# P1AM-ISOLATED-2X2-GPIO.net
KiCad netlist of a schematic drawn in EAGLE
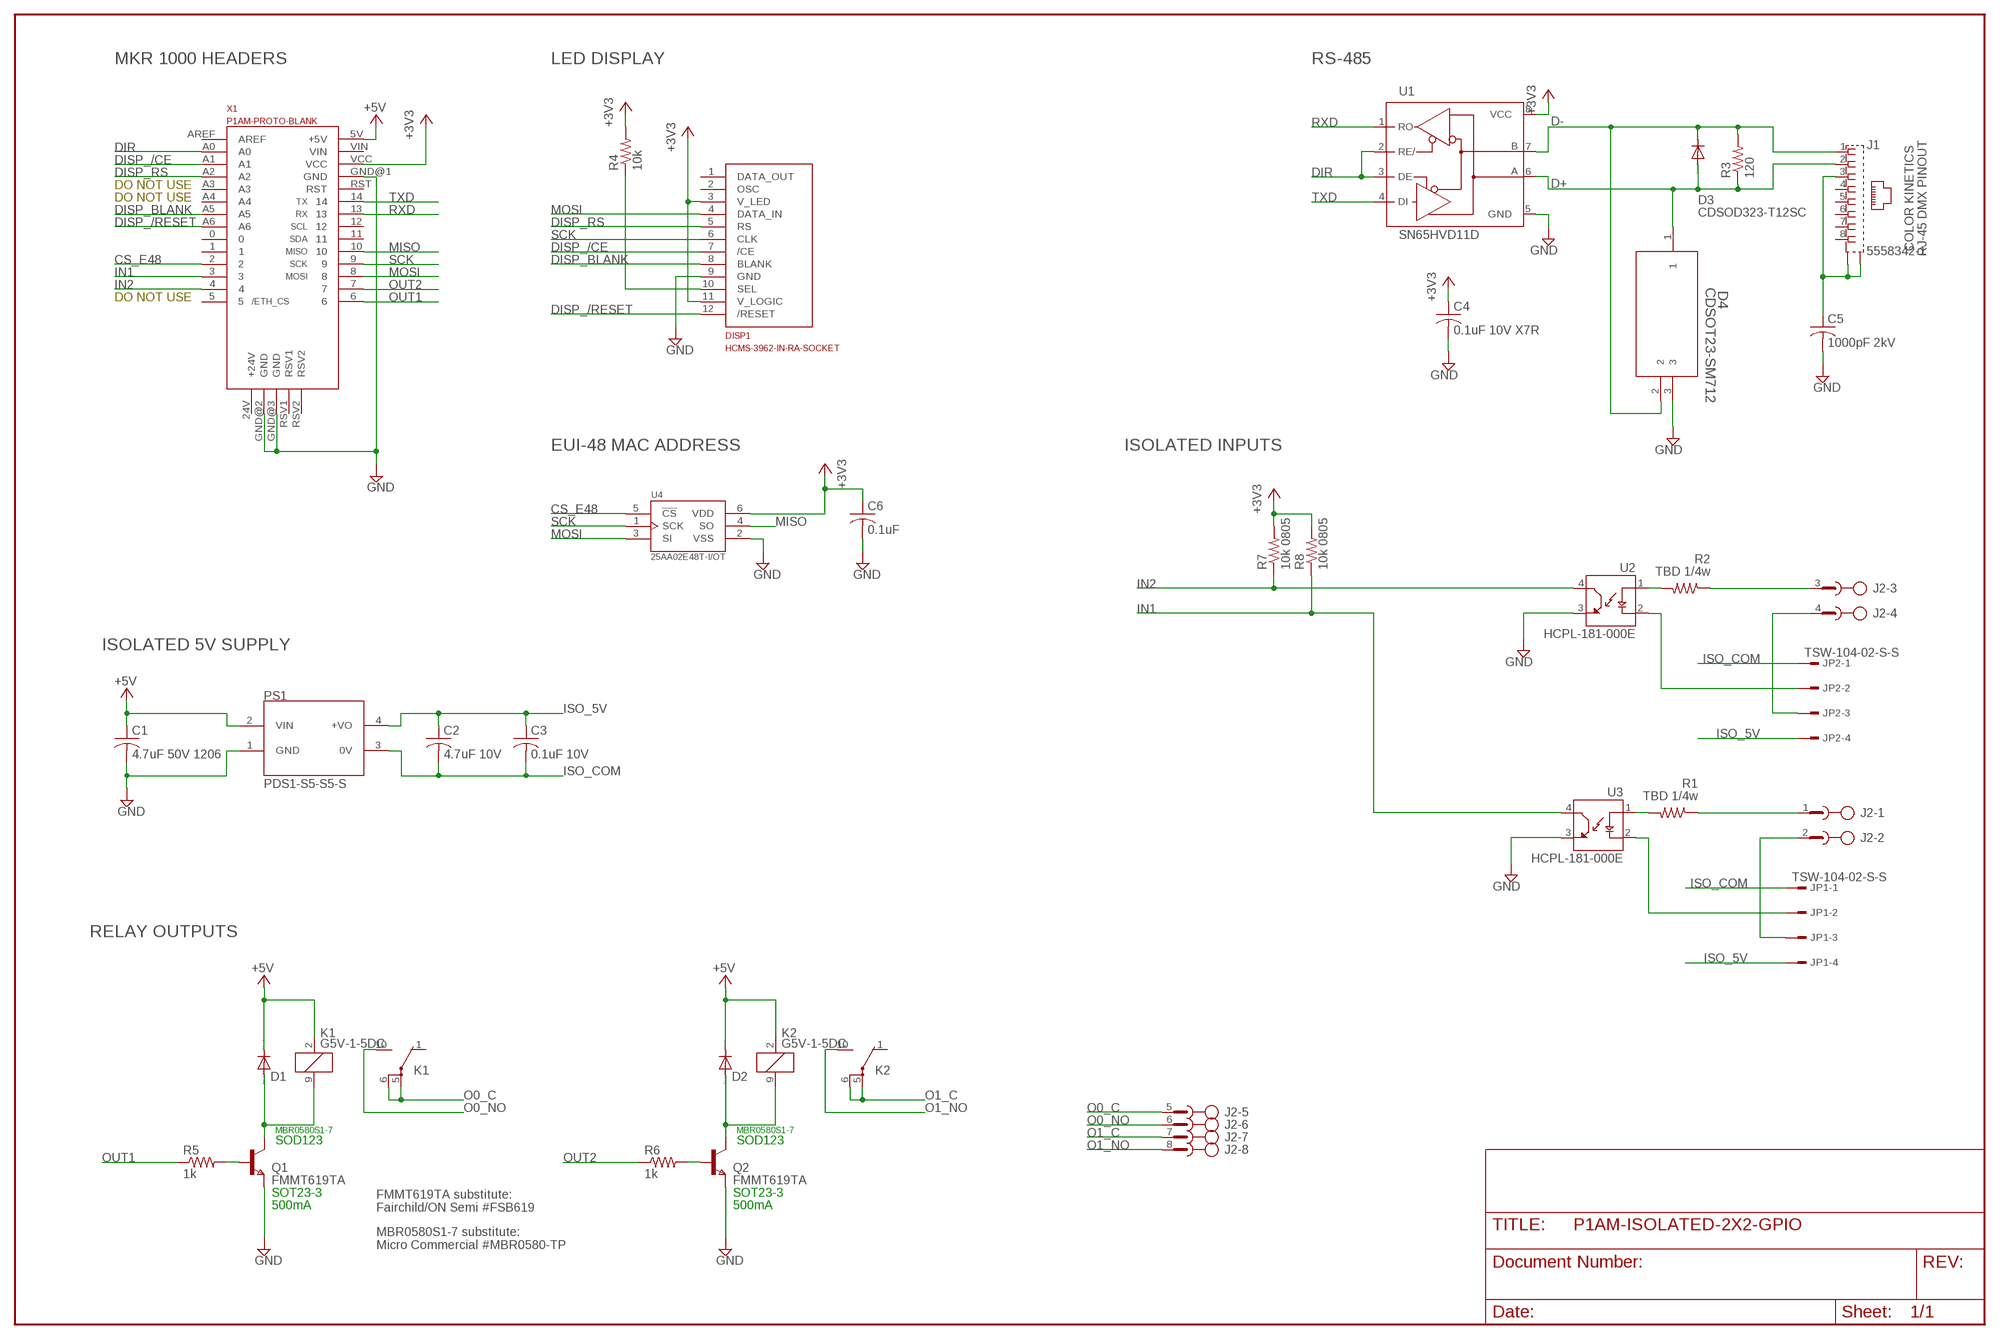
[diagram p0: schematic, sheet 1]

(export (version "E")
  (design (tool "Eeschema 10.0.6"))
  (components
    (comp (ref "C1")
      (value "4.7uF 50V 1206")
      (footprint "eagle-import:C1206K")
      (fields (field (name "MFR_PART_NO") "C1206C475K5RACTU"))
      (libsource (lib "eagle-import") (part "C-USC1206K"))
    )
    (comp (ref "C2")
      (value "4.7uF 10V")
      (footprint "eagle-import:C1206K")
      (libsource (lib "eagle-import") (part "C-USC1206K"))
    )
    (comp (ref "C3")
      (value "0.1uF 10V")
      (footprint "eagle-import:C1206K")
      (fields (field (name "MFR_PART_NO") "C1206C475K5RACTU"))
      (libsource (lib "eagle-import") (part "C-USC1206K"))
    )
    (comp (ref "C4")
      (value "0.1uF 10V X7R")
      (footprint "eagle-import:C0805")
      (libsource (lib "eagle-import") (part "C-USC0805"))
    )
    (comp (ref "C5")
      (value "1000pF 2kV")
      (footprint "eagle-import:C1206K")
      (libsource (lib "eagle-import") (part "C-USC1206K"))
    )
    (comp (ref "C6")
      (value "0.1uF")
      (footprint "eagle-import:C0603")
      (libsource (lib "eagle-import") (part "C-USC0603"))
    )
    (comp (ref "D1")
      (value "1N4148W-TP")
      (footprint "eagle-import:SOD123")
      (fields (field (name "MFR") "DIODES INC") (field (name "MFR_PART_NO") "MBR0580S1-7"))
      (libsource (lib "eagle-import") (part "DIODE-SOD123"))
    )
    (comp (ref "D2")
      (value "1N4148W-TP")
      (footprint "eagle-import:SOD123")
      (fields (field (name "MFR") "DIODES INC") (field (name "MFR_PART_NO") "MBR0580S1-7"))
      (libsource (lib "eagle-import") (part "DIODE-SOD123"))
    )
    (comp (ref "D3")
      (value "CDSOD323-T12SC")
      (footprint "eagle-import:SOD323-W")
      (libsource (lib "eagle-import") (part "DIODE-SOD323-W"))
    )
    (comp (ref "D4")
      (value "CDSOT23-SM712")
      (footprint "eagle-import:SOT_SM712")
      (libsource (lib "eagle-import") (part "CDSOT23-SM712"))
    )
    (comp (ref "DISP1")
      (value "HCMS-3962-IN-RA-SOCKET")
      (footprint "eagle-import:299-43-312-11-001000")
      (libsource (lib "eagle-import") (part "HCMS-3962-IN-RA-SOCKET"))
    )
    (comp (ref "J1")
      (value "5558342-1")
      (footprint "eagle-import:TE_5558342-1")
      (fields (field (name "DIGI-KEY_PART_NUMBER") "A31466-ND") (field (name "MF") "TE Connectivity"))
      (libsource (lib "eagle-import") (part "5558342-1"))
    )
    (comp (ref "J2")
      (value "PHOENIX-XXXXXXX-TERM-BLOCK-HDR-8POS-90DEG-3.5MM")
      (footprint "eagle-import:PHOENIX-XXXXXXX-TERM-BLOCK-HDR-8POS-90DEG-3.5MM")
      (libsource (lib "eagle-import") (part "PHOENIX-XXXXXXX-TERM-BLOCK-HDR-8POS-90DEG-3.5MM"))
    )
    (comp (ref "JP1")
      (value "TSW-104-02-S-S")
      (footprint "eagle-import:TSW-104-02-S-S")
      (libsource (lib "eagle-import") (part "TSW-104-02-S-S"))
    )
    (comp (ref "JP2")
      (value "TSW-104-02-S-S")
      (footprint "eagle-import:TSW-104-02-S-S")
      (libsource (lib "eagle-import") (part "TSW-104-02-S-S"))
    )
    (comp (ref "K1")
      (value "G5V-1-5DC")
      (footprint "eagle-import:G5V1")
      (fields
        (field (name "MPN") "G5V-1-DC24")
        (field (name "MFR") "OMRON")
        (field (name "MFR_PART_NO") "G5V-1-DC5")
      )
      (libsource (lib "eagle-import") (part "G5V1"))
    )
    (comp (ref "K2")
      (value "G5V-1-5DC")
      (footprint "eagle-import:G5V1")
      (fields
        (field (name "MPN") "G5V-1-DC24")
        (field (name "MFR") "OMRON")
        (field (name "MFR_PART_NO") "G5V-1-DC5")
      )
      (libsource (lib "eagle-import") (part "G5V1"))
    )
    (comp (ref "PS1")
      (value "PDS1-S5-S5-S")
      (footprint "eagle-import:CONV_PDS1-S5-S5-S")
      (fields (field (name "MF") "CUI") (field (name "MP") "PDS1-S12-S12-S"))
      (libsource (lib "eagle-import") (part "PDS1-S5-S5-S"))
    )
    (comp (ref "Q1")
      (value "FMMT619TA")
      (footprint "eagle-import:SOT-23")
      (fields (field (name "MPN") "DSS20201L-7") (field (name "MFR") "DIODES INC"))
      (libsource (lib "eagle-import") (part "NPNSOT23"))
    )
    (comp (ref "Q2")
      (value "FMMT619TA")
      (footprint "eagle-import:SOT-23")
      (fields (field (name "MPN") "DSS20201L-7") (field (name "MFR") "DIODES INC"))
      (libsource (lib "eagle-import") (part "NPNSOT23"))
    )
    (comp (ref "R1")
      (value "TBD 1/4w")
      (footprint "eagle-import:R1206")
      (libsource (lib "eagle-import") (part "R-US_R1206"))
    )
    (comp (ref "R2")
      (value "TBD 1/4w")
      (footprint "eagle-import:R1206")
      (libsource (lib "eagle-import") (part "R-US_R1206"))
    )
    (comp (ref "R3")
      (value "120")
      (footprint "eagle-import:R0805")
      (libsource (lib "eagle-import") (part "R-US_R0805"))
    )
    (comp (ref "R4")
      (value "10k")
      (footprint "eagle-import:R0805")
      (libsource (lib "eagle-import") (part "R-US_R0805"))
    )
    (comp (ref "R5")
      (value "1k")
      (footprint "eagle-import:R1206")
      (fields (field (name "MFR") "BOURNS") (field (name "MFR_PART_NO") "CR1206-JW-102ELF"))
      (libsource (lib "eagle-import") (part "R-US_R1206"))
    )
    (comp (ref "R6")
      (value "1k")
      (footprint "eagle-import:R1206")
      (fields (field (name "MFR") "BOURNS") (field (name "MFR_PART_NO") "CR1206-JW-102ELF"))
      (libsource (lib "eagle-import") (part "R-US_R1206"))
    )
    (comp (ref "R7")
      (value "10k 0805")
      (footprint "eagle-import:R0805")
      (libsource (lib "eagle-import") (part "resistor_R-US_R0805"))
    )
    (comp (ref "R8")
      (value "10k 0805")
      (footprint "eagle-import:R0805")
      (libsource (lib "eagle-import") (part "resistor_R-US_R0805"))
    )
    (comp (ref "U1")
      (value "SN65HVD11D")
      (footprint "eagle-import:SO08")
      (fields (field (name "MPN") "MAX3468CSA+"))
      (libsource (lib "eagle-import") (part "MAX34SA68C"))
    )
    (comp (ref "U2")
      (value "HCPL-181-000E")
      (footprint "eagle-import:SOIC254P675X240-4N")
      (fields (field (name "DIGI-KEY_PART_NUMBER") "516-1646-1-ND") (field (name "MF") "Broadcom Limited"))
      (libsource (lib "eagle-import") (part "HCPL-181-000E"))
    )
    (comp (ref "U3")
      (value "HCPL-181-000E")
      (footprint "eagle-import:SOIC254P675X240-4N")
      (fields (field (name "DIGI-KEY_PART_NUMBER") "516-1646-1-ND") (field (name "MF") "Broadcom Limited"))
      (libsource (lib "eagle-import") (part "HCPL-181-000E"))
    )
    (comp (ref "U4")
      (value "25AA02E48T-I/OT")
      (footprint "eagle-import:SOT95P270X145-6N")
      (fields (field (name "DIGI-KEY_PART_NUMBER") "25AA02E48T-I/OTCT-ND") (field (name "MF") "Microchip"))
      (libsource (lib "eagle-import") (part "25AA02E48T-I/OT"))
    )
    (comp (ref "X1")
      (value "P1AM-PROTO-BLANK")
      (footprint "eagle-import:P1AM-PROTO-BLANK")
      (libsource (lib "eagle-import") (part "P1AM-PROTO-BLANK"))
    )
  )
  (nets
    (net (code "1") (name "+3V3") (class "Default")
      (node (ref "C4") (pin "1") (pinfunction "1_1") (pintype "passive"))
      (node (ref "C6") (pin "1") (pinfunction "1_1") (pintype "passive"))
      (node (ref "DISP1") (pin "11") (pinfunction "V_LOGIC_11") (pintype "bidirectional"))
      (node (ref "DISP1") (pin "3") (pinfunction "V_LED_3") (pintype "bidirectional"))
      (node (ref "R4") (pin "2") (pinfunction "2_2") (pintype "passive"))
      (node (ref "R7") (pin "2") (pinfunction "2_2") (pintype "passive"))
      (node (ref "R8") (pin "2") (pinfunction "2_2") (pintype "passive"))
      (node (ref "U1") (pin "8") (pinfunction "VCC_8") (pintype "power_in"))
      (node (ref "U4") (pin "6") (pinfunction "VDD_6") (pintype "power_in"))
      (node (ref "X1") (pin "VCC") (pinfunction "VCC_VCC") (pintype "bidirectional"))
    )
    (net (code "2") (name "+5V") (class "Default")
      (node (ref "C1") (pin "1") (pinfunction "1_1") (pintype "passive"))
      (node (ref "D1") (pin "C") (pinfunction "C_C") (pintype "passive"))
      (node (ref "D2") (pin "C") (pinfunction "C_C") (pintype "passive"))
      (node (ref "K1") (pin "2") (pinfunction "1_2") (pintype "passive"))
      (node (ref "K2") (pin "2") (pinfunction "1_2") (pintype "passive"))
      (node (ref "PS1") (pin "2") (pinfunction "VIN_2") (pintype "input"))
      (node (ref "X1") (pin "5V") (pinfunction "+5V_5V") (pintype "bidirectional"))
    )
    (net (code "3") (name "/CS_E48") (class "Default")
      (node (ref "U4") (pin "5") (pinfunction "~{CS}_5") (pintype "input"))
      (node (ref "X1") (pin "2") (pinfunction "2_2") (pintype "bidirectional"))
    )
    (net (code "4") (name "/D+") (class "Default")
      (node (ref "D3") (pin "A") (pinfunction "A_A") (pintype "passive"))
      (node (ref "D4") (pin "1") (pinfunction "1_1") (pintype "passive"))
      (node (ref "J1") (pin "2") (pinfunction "2_2") (pintype "passive"))
      (node (ref "R3") (pin "1") (pinfunction "1_1") (pintype "passive"))
      (node (ref "U1") (pin "6") (pinfunction "A_6") (pintype "passive"))
    )
    (net (code "5") (name "/D-") (class "Default")
      (node (ref "D3") (pin "C") (pinfunction "C_C") (pintype "passive"))
      (node (ref "D4") (pin "2") (pinfunction "2_2") (pintype "passive"))
      (node (ref "J1") (pin "1") (pinfunction "1_1") (pintype "passive"))
      (node (ref "R3") (pin "2") (pinfunction "2_2") (pintype "passive"))
      (node (ref "U1") (pin "7") (pinfunction "B_7") (pintype "passive"))
    )
    (net (code "6") (name "/DIR") (class "Default")
      (node (ref "U1") (pin "2") (pinfunction "RE/_2") (pintype "input"))
      (node (ref "U1") (pin "3") (pinfunction "DE_3") (pintype "input"))
      (node (ref "X1") (pin "A0") (pinfunction "A0_A0") (pintype "bidirectional"))
    )
    (net (code "7") (name "/DISP_BLANK") (class "Default")
      (node (ref "DISP1") (pin "8") (pinfunction "BLANK_8") (pintype "bidirectional"))
      (node (ref "X1") (pin "A5") (pinfunction "A5_A5") (pintype "bidirectional"))
    )
    (net (code "8") (name "/DISP_RS") (class "Default")
      (node (ref "DISP1") (pin "5") (pinfunction "RS_5") (pintype "bidirectional"))
      (node (ref "X1") (pin "A2") (pinfunction "A2_A2") (pintype "bidirectional"))
    )
    (net (code "9") (name "/DISP_{slash}CE") (class "Default")
      (node (ref "DISP1") (pin "7") (pinfunction "/CE_7") (pintype "bidirectional"))
      (node (ref "X1") (pin "A1") (pinfunction "A1_A1") (pintype "bidirectional"))
    )
    (net (code "10") (name "/DISP_{slash}RESET") (class "Default")
      (node (ref "DISP1") (pin "12") (pinfunction "/RESET_12") (pintype "bidirectional"))
      (node (ref "X1") (pin "A6") (pinfunction "A6_A6") (pintype "bidirectional"))
    )
    (net (code "11") (name "/IN1") (class "Default")
      (node (ref "R8") (pin "1") (pinfunction "1_1") (pintype "passive"))
      (node (ref "U3") (pin "4") (pinfunction "COLLECTOR_4") (pintype "passive"))
      (node (ref "X1") (pin "3") (pinfunction "3_3") (pintype "bidirectional"))
    )
    (net (code "12") (name "/IN2") (class "Default")
      (node (ref "R7") (pin "1") (pinfunction "1_1") (pintype "passive"))
      (node (ref "U2") (pin "4") (pinfunction "COLLECTOR_4") (pintype "passive"))
      (node (ref "X1") (pin "4") (pinfunction "4_4") (pintype "bidirectional"))
    )
    (net (code "13") (name "/ISO_5V") (class "Default")
      (node (ref "C2") (pin "1") (pinfunction "1_1") (pintype "passive"))
      (node (ref "C3") (pin "1") (pinfunction "1_1") (pintype "passive"))
      (node (ref "JP1") (pin "4") (pinfunction "1_4") (pintype "passive"))
      (node (ref "JP2") (pin "4") (pinfunction "1_4") (pintype "passive"))
      (node (ref "PS1") (pin "4") (pinfunction "+VO_4") (pintype "output"))
    )
    (net (code "14") (name "/ISO_COM") (class "Default")
      (node (ref "C2") (pin "2") (pinfunction "2_2") (pintype "passive"))
      (node (ref "C3") (pin "2") (pinfunction "2_2") (pintype "passive"))
      (node (ref "JP1") (pin "1") (pinfunction "1_1") (pintype "passive"))
      (node (ref "JP2") (pin "1") (pinfunction "1_1") (pintype "passive"))
      (node (ref "PS1") (pin "3") (pinfunction "0V_3") (pintype "power_in"))
    )
    (net (code "15") (name "/MISO") (class "Default")
      (node (ref "U4") (pin "4") (pinfunction "SO_4") (pintype "output"))
      (node (ref "X1") (pin "10") (pinfunction "10_10") (pintype "bidirectional"))
    )
    (net (code "16") (name "/MOSI") (class "Default")
      (node (ref "DISP1") (pin "4") (pinfunction "DATA_IN_4") (pintype "bidirectional"))
      (node (ref "U4") (pin "3") (pinfunction "SI_3") (pintype "input"))
      (node (ref "X1") (pin "8") (pinfunction "8_8") (pintype "bidirectional"))
    )
    (net (code "17") (name "/O0_C") (class "Default")
      (node (ref "J2") (pin "5") (pinfunction "1_5") (pintype "passive"))
      (node (ref "K1") (pin "5") (pinfunction "P_5") (pintype "passive"))
      (node (ref "K1") (pin "6") (pinfunction "P_6") (pintype "passive"))
    )
    (net (code "18") (name "/O0_NO") (class "Default")
      (node (ref "J2") (pin "6") (pinfunction "1_6") (pintype "passive"))
      (node (ref "K1") (pin "10") (pinfunction "S_10") (pintype "passive"))
    )
    (net (code "19") (name "/O1_C") (class "Default")
      (node (ref "J2") (pin "7") (pinfunction "1_7") (pintype "passive"))
      (node (ref "K2") (pin "5") (pinfunction "P_5") (pintype "passive"))
      (node (ref "K2") (pin "6") (pinfunction "P_6") (pintype "passive"))
    )
    (net (code "20") (name "/O1_NO") (class "Default")
      (node (ref "J2") (pin "8") (pinfunction "1_8") (pintype "passive"))
      (node (ref "K2") (pin "10") (pinfunction "S_10") (pintype "passive"))
    )
    (net (code "21") (name "/OUT1") (class "Default")
      (node (ref "R5") (pin "1") (pinfunction "1_1") (pintype "passive"))
      (node (ref "X1") (pin "6") (pinfunction "6_6") (pintype "bidirectional"))
    )
    (net (code "22") (name "/OUT2") (class "Default")
      (node (ref "R6") (pin "1") (pinfunction "1_1") (pintype "passive"))
      (node (ref "X1") (pin "7") (pinfunction "7_7") (pintype "bidirectional"))
    )
    (net (code "23") (name "/RXD") (class "Default")
      (node (ref "U1") (pin "1") (pinfunction "RO_1") (pintype "output"))
      (node (ref "X1") (pin "13") (pinfunction "13_13") (pintype "bidirectional"))
    )
    (net (code "24") (name "/SCK") (class "Default")
      (node (ref "DISP1") (pin "6") (pinfunction "CLK_6") (pintype "bidirectional"))
      (node (ref "U4") (pin "1") (pinfunction "SCK_1") (pintype "input"))
      (node (ref "X1") (pin "9") (pinfunction "9_9") (pintype "bidirectional"))
    )
    (net (code "25") (name "/TXD") (class "Default")
      (node (ref "U1") (pin "4") (pinfunction "DI_4") (pintype "input"))
      (node (ref "X1") (pin "14") (pinfunction "14_14") (pintype "bidirectional"))
    )
    (net (code "26") (name "GND") (class "Default")
      (node (ref "C1") (pin "2") (pinfunction "2_2") (pintype "passive"))
      (node (ref "C4") (pin "2") (pinfunction "2_2") (pintype "passive"))
      (node (ref "C5") (pin "2") (pinfunction "2_2") (pintype "passive"))
      (node (ref "C6") (pin "2") (pinfunction "2_2") (pintype "passive"))
      (node (ref "D4") (pin "3") (pinfunction "3_3") (pintype "passive"))
      (node (ref "DISP1") (pin "9") (pinfunction "GND_9") (pintype "bidirectional"))
      (node (ref "PS1") (pin "1") (pinfunction "GND_1") (pintype "power_in"))
      (node (ref "Q1") (pin "2") (pinfunction "E_2") (pintype "passive"))
      (node (ref "Q2") (pin "2") (pinfunction "E_2") (pintype "passive"))
      (node (ref "U1") (pin "5") (pinfunction "GND_5") (pintype "power_in"))
      (node (ref "U2") (pin "3") (pinfunction "EMITTER_3") (pintype "passive"))
      (node (ref "U3") (pin "3") (pinfunction "EMITTER_3") (pintype "passive"))
      (node (ref "U4") (pin "2") (pinfunction "VSS_2") (pintype "power_in"))
      (node (ref "X1") (pin "GND@1") (pinfunction "GND_GND@1") (pintype "bidirectional"))
      (node (ref "X1") (pin "GND@2") (pinfunction "GND_GND@2") (pintype "bidirectional"))
      (node (ref "X1") (pin "GND@3") (pinfunction "GND_GND@3") (pintype "bidirectional"))
    )
    (net (code "27") (name "Net-(DISP1-SEL)") (class "Default")
      (node (ref "DISP1") (pin "10") (pinfunction "SEL_10") (pintype "bidirectional"))
      (node (ref "R4") (pin "1") (pinfunction "1_1") (pintype "passive"))
    )
    (net (code "28") (name "Net-(J1-S1)") (class "Default")
      (node (ref "C5") (pin "1") (pinfunction "1_1") (pintype "passive"))
      (node (ref "J1") (pin "3") (pinfunction "3_3") (pintype "passive"))
      (node (ref "J1") (pin "SH1") (pinfunction "S1_SH1") (pintype "passive"))
      (node (ref "J1") (pin "SH2") (pinfunction "S2_SH2") (pintype "passive"))
    )
    (net (code "29") (name "Net-(J2-Pad1)") (class "Default")
      (node (ref "J2") (pin "1") (pinfunction "1_1") (pintype "passive"))
      (node (ref "R1") (pin "1") (pinfunction "1_1") (pintype "passive"))
    )
    (net (code "30") (name "Net-(J2B-1)") (class "Default")
      (node (ref "J2") (pin "2") (pinfunction "1_2") (pintype "passive"))
      (node (ref "JP1") (pin "3") (pinfunction "1_3") (pintype "passive"))
    )
    (net (code "31") (name "Net-(J2C-1)") (class "Default")
      (node (ref "J2") (pin "3") (pinfunction "1_3") (pintype "passive"))
      (node (ref "R2") (pin "1") (pinfunction "1_1") (pintype "passive"))
    )
    (net (code "32") (name "Net-(J2D-1)") (class "Default")
      (node (ref "J2") (pin "4") (pinfunction "1_4") (pintype "passive"))
      (node (ref "JP2") (pin "3") (pinfunction "1_3") (pintype "passive"))
    )
    (net (code "33") (name "Net-(JP1B-1)") (class "Default")
      (node (ref "JP1") (pin "2") (pinfunction "1_2") (pintype "passive"))
      (node (ref "U3") (pin "2") (pinfunction "CATHODE_2") (pintype "passive"))
    )
    (net (code "34") (name "Net-(JP2B-1)") (class "Default")
      (node (ref "JP2") (pin "2") (pinfunction "1_2") (pintype "passive"))
      (node (ref "U2") (pin "2") (pinfunction "CATHODE_2") (pintype "passive"))
    )
    (net (code "35") (name "Net-(K1A-2)") (class "Default")
      (node (ref "D1") (pin "A") (pinfunction "A_A") (pintype "passive"))
      (node (ref "K1") (pin "9") (pinfunction "2_9") (pintype "passive"))
      (node (ref "Q1") (pin "1") (pinfunction "C_1") (pintype "passive"))
    )
    (net (code "36") (name "Net-(K2A-2)") (class "Default")
      (node (ref "D2") (pin "A") (pinfunction "A_A") (pintype "passive"))
      (node (ref "K2") (pin "9") (pinfunction "2_9") (pintype "passive"))
      (node (ref "Q2") (pin "1") (pinfunction "C_1") (pintype "passive"))
    )
    (net (code "37") (name "Net-(Q1-B)") (class "Default")
      (node (ref "Q1") (pin "3") (pinfunction "B_3") (pintype "passive"))
      (node (ref "R5") (pin "2") (pinfunction "2_2") (pintype "passive"))
    )
    (net (code "38") (name "Net-(Q2-B)") (class "Default")
      (node (ref "Q2") (pin "3") (pinfunction "B_3") (pintype "passive"))
      (node (ref "R6") (pin "2") (pinfunction "2_2") (pintype "passive"))
    )
    (net (code "39") (name "Net-(U2-ANODE)") (class "Default")
      (node (ref "R2") (pin "2") (pinfunction "2_2") (pintype "passive"))
      (node (ref "U2") (pin "1") (pinfunction "ANODE_1") (pintype "passive"))
    )
    (net (code "40") (name "Net-(U3-ANODE)") (class "Default")
      (node (ref "R1") (pin "2") (pinfunction "2_2") (pintype "passive"))
      (node (ref "U3") (pin "1") (pinfunction "ANODE_1") (pintype "passive"))
    )
    (net (code "41") (name "unconnected-(DISP1-DATA_OUT-Pad1)") (class "Default")
      (node (ref "DISP1") (pin "1") (pinfunction "DATA_OUT_1") (pintype "bidirectional"))
    )
    (net (code "42") (name "unconnected-(DISP1-OSC-Pad2)") (class "Default")
      (node (ref "DISP1") (pin "2") (pinfunction "OSC_2") (pintype "bidirectional"))
    )
    (net (code "43") (name "unconnected-(J1-Pad4)") (class "Default")
      (node (ref "J1") (pin "4") (pinfunction "4_4") (pintype "passive"))
    )
    (net (code "44") (name "unconnected-(J1-Pad5)") (class "Default")
      (node (ref "J1") (pin "5") (pinfunction "5_5") (pintype "passive"))
    )
    (net (code "45") (name "unconnected-(J1-Pad6)") (class "Default")
      (node (ref "J1") (pin "6") (pinfunction "6_6") (pintype "passive"))
    )
    (net (code "46") (name "unconnected-(J1-Pad7)") (class "Default")
      (node (ref "J1") (pin "7") (pinfunction "7_7") (pintype "passive"))
    )
    (net (code "47") (name "unconnected-(J1-Pad8)") (class "Default")
      (node (ref "J1") (pin "8") (pinfunction "8_8") (pintype "passive"))
    )
    (net (code "48") (name "unconnected-(K1B-O-Pad1)") (class "Default")
      (node (ref "K1") (pin "1") (pinfunction "O_1") (pintype "passive"))
    )
    (net (code "49") (name "unconnected-(K2B-O-Pad1)") (class "Default")
      (node (ref "K2") (pin "1") (pinfunction "O_1") (pintype "passive"))
    )
    (net (code "50") (name "unconnected-(X1-+24V-Pad24V)") (class "Default")
      (node (ref "X1") (pin "24V") (pinfunction "+24V_24V") (pintype "bidirectional"))
    )
    (net (code "51") (name "unconnected-(X1-Pad0)") (class "Default")
      (node (ref "X1") (pin "0") (pinfunction "0_0") (pintype "bidirectional"))
    )
    (net (code "52") (name "unconnected-(X1-Pad1)") (class "Default")
      (node (ref "X1") (pin "1") (pinfunction "1_1") (pintype "bidirectional"))
    )
    (net (code "53") (name "unconnected-(X1-Pad5)") (class "Default")
      (node (ref "X1") (pin "5") (pinfunction "5_5") (pintype "bidirectional"))
    )
    (net (code "54") (name "unconnected-(X1-Pad11)") (class "Default")
      (node (ref "X1") (pin "11") (pinfunction "11_11") (pintype "bidirectional"))
    )
    (net (code "55") (name "unconnected-(X1-Pad12)") (class "Default")
      (node (ref "X1") (pin "12") (pinfunction "12_12") (pintype "bidirectional"))
    )
    (net (code "56") (name "unconnected-(X1-PadA3)") (class "Default")
      (node (ref "X1") (pin "A3") (pinfunction "A3_A3") (pintype "bidirectional"))
    )
    (net (code "57") (name "unconnected-(X1-PadA4)") (class "Default")
      (node (ref "X1") (pin "A4") (pinfunction "A4_A4") (pintype "bidirectional"))
    )
    (net (code "58") (name "unconnected-(X1-PadAREF)") (class "Default")
      (node (ref "X1") (pin "AREF") (pinfunction "AREF_AREF") (pintype "bidirectional"))
    )
    (net (code "59") (name "unconnected-(X1-PadRST)") (class "Default")
      (node (ref "X1") (pin "RST") (pinfunction "RST_RST") (pintype "bidirectional"))
    )
    (net (code "60") (name "unconnected-(X1-PadRSV1)") (class "Default")
      (node (ref "X1") (pin "RSV1") (pinfunction "RSV1_RSV1") (pintype "bidirectional"))
    )
    (net (code "61") (name "unconnected-(X1-PadRSV2)") (class "Default")
      (node (ref "X1") (pin "RSV2") (pinfunction "RSV2_RSV2") (pintype "bidirectional"))
    )
    (net (code "62") (name "unconnected-(X1-PadVIN)") (class "Default")
      (node (ref "X1") (pin "VIN") (pinfunction "VIN_VIN") (pintype "bidirectional"))
    )
  )
)
